# Rocketometer2148_LSM330DLC.net
KiCad netlist of a schematic drawn in EAGLE
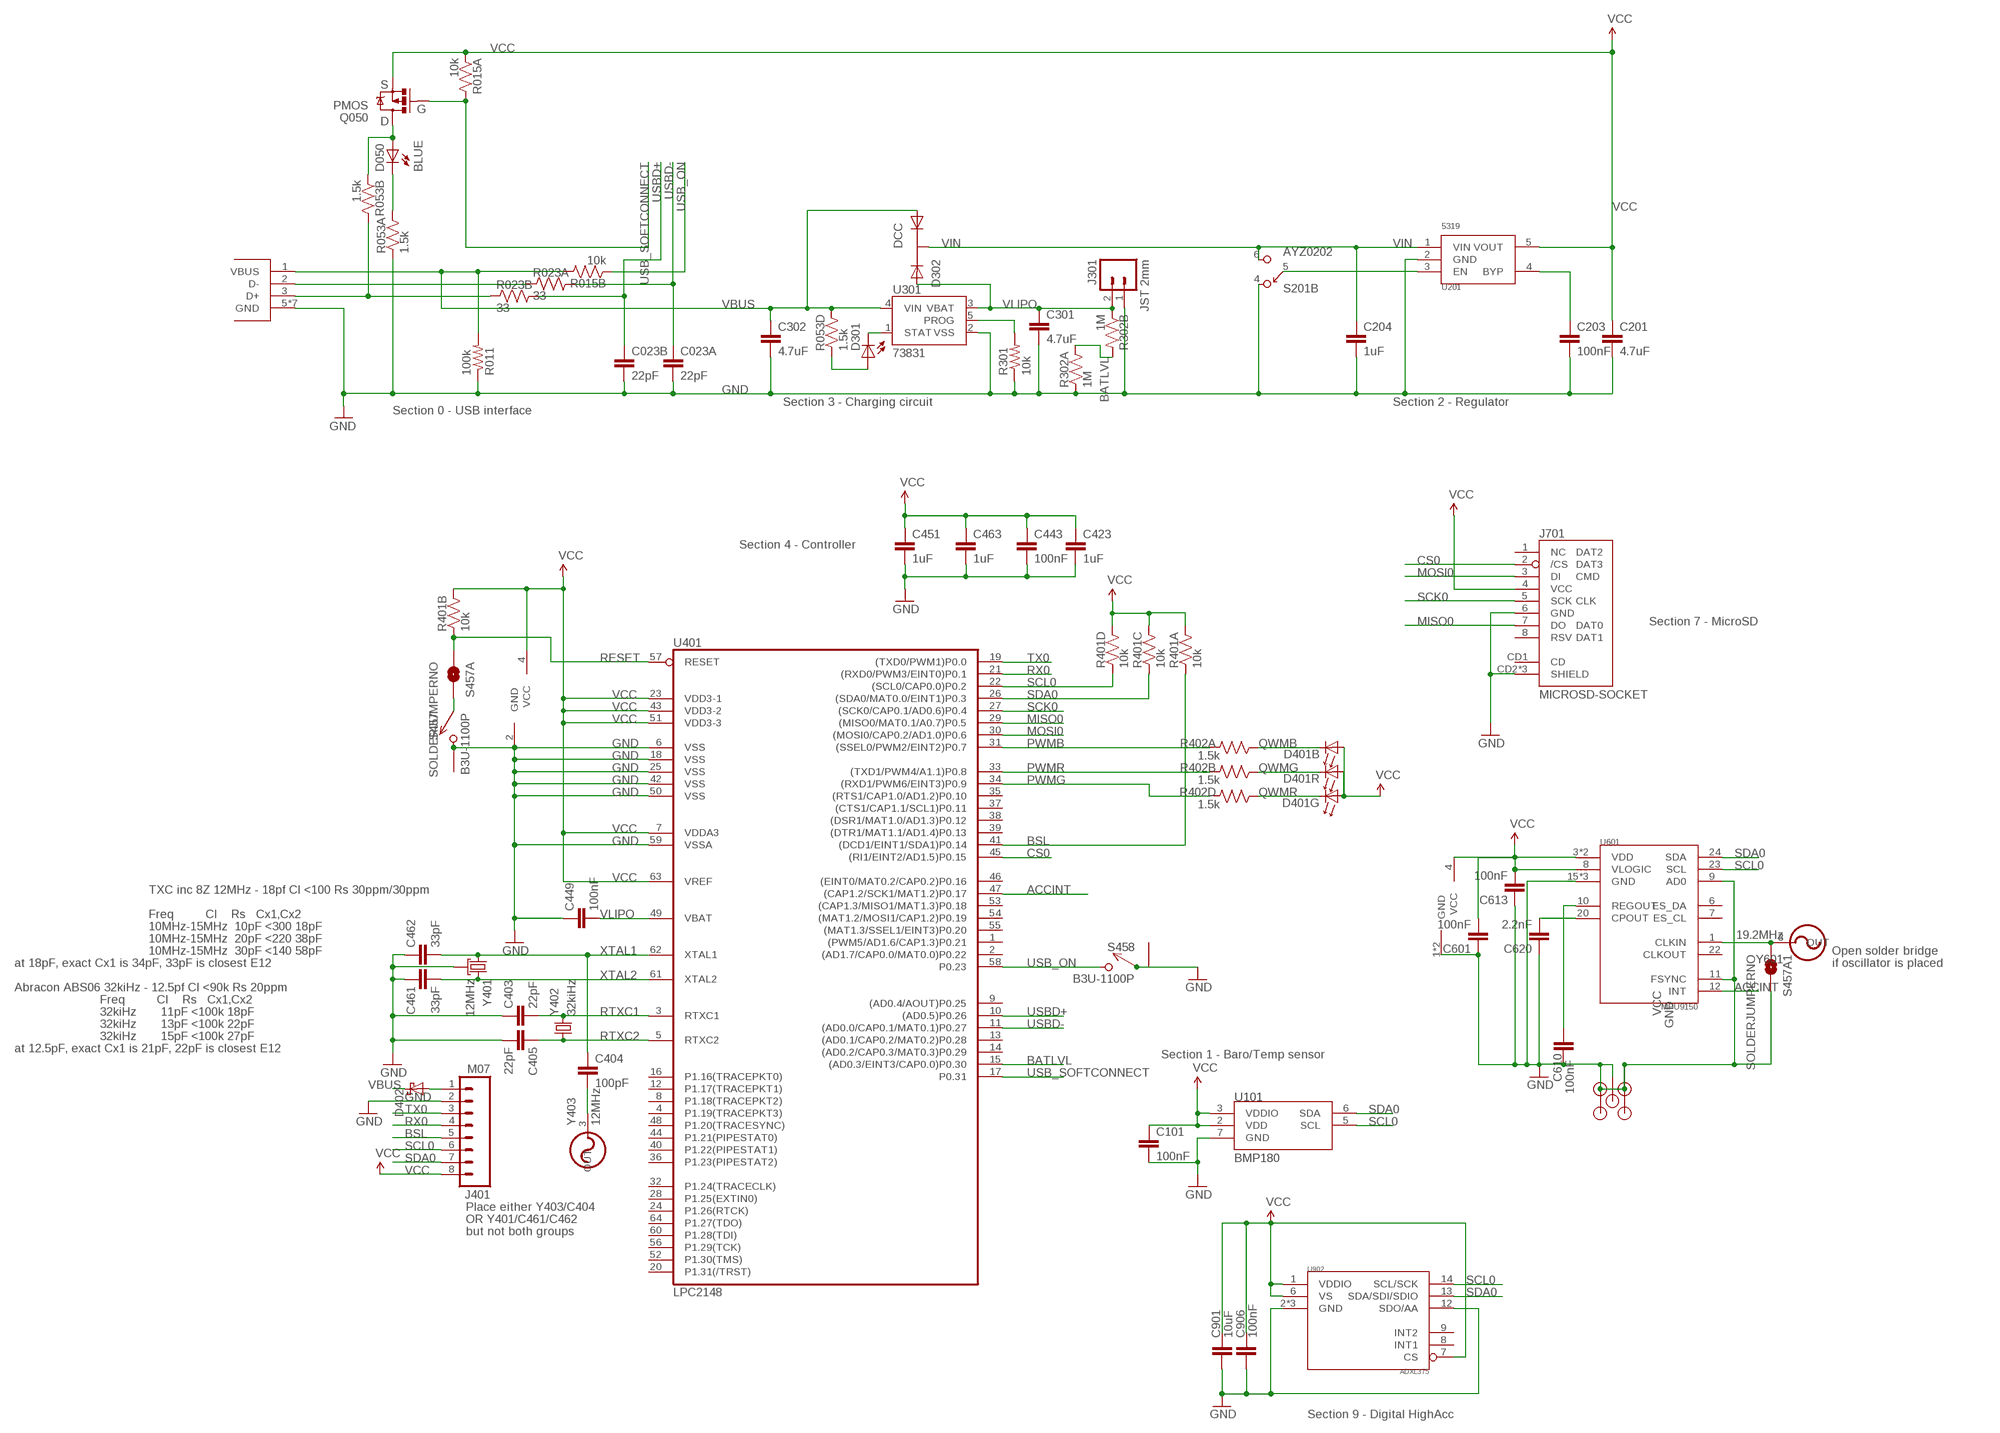
[diagram p0: schematic, sheet 1]

(export (version "E")
  (design (tool "Eeschema 10.0.6"))
  (components
    (comp (ref "C023")
      (value "22pF")
      (footprint "eagle-import:CKCM25")
      (fields (field (name "DIGIKEY") "445-1860-1-ND"))
      (libsource (lib "eagle-import") (part "CKCM25"))
    )
    (comp (ref "C101")
      (value "100nF")
      (footprint "eagle-import:0402-CAP")
      (libsource (lib "eagle-import") (part "CAP0402-CAP"))
    )
    (comp (ref "C201")
      (value "4.7uF")
      (footprint "eagle-import:0402-CAP")
      (libsource (lib "eagle-import") (part "CAP0402-CAP"))
    )
    (comp (ref "C203")
      (value "100nF")
      (footprint "eagle-import:0402-CAP")
      (libsource (lib "eagle-import") (part "CAP0402-CAP"))
    )
    (comp (ref "C204")
      (value "1uF")
      (footprint "eagle-import:0402-CAP")
      (libsource (lib "eagle-import") (part "CAP0402-CAP"))
    )
    (comp (ref "C301")
      (value "4.7uF")
      (footprint "eagle-import:0402-CAP")
      (libsource (lib "eagle-import") (part "CAP0402-CAP"))
    )
    (comp (ref "C302")
      (value "4.7uF")
      (footprint "eagle-import:0402-CAP")
      (libsource (lib "eagle-import") (part "CAP0402-CAP"))
    )
    (comp (ref "C403")
      (value "22pF")
      (footprint "eagle-import:0402-CAP")
      (libsource (lib "eagle-import") (part "CAP0402-CAP"))
    )
    (comp (ref "C404")
      (value "100pF")
      (footprint "eagle-import:0402-CAP")
      (libsource (lib "eagle-import") (part "CAP0402-CAP"))
    )
    (comp (ref "C405")
      (value "22pF")
      (footprint "eagle-import:0402-CAP")
      (libsource (lib "eagle-import") (part "CAP0402-CAP"))
    )
    (comp (ref "C423")
      (value "1uF")
      (footprint "eagle-import:0402-CAP")
      (libsource (lib "eagle-import") (part "CAP0402-CAP"))
    )
    (comp (ref "C443")
      (value "100nF")
      (footprint "eagle-import:0402-CAP")
      (libsource (lib "eagle-import") (part "CAP0402-CAP"))
    )
    (comp (ref "C449")
      (value "100nF")
      (footprint "eagle-import:0402-CAP")
      (libsource (lib "eagle-import") (part "CAP0402-CAP"))
    )
    (comp (ref "C451")
      (value "1uF")
      (footprint "eagle-import:0402-CAP")
      (libsource (lib "eagle-import") (part "CAP0402-CAP"))
    )
    (comp (ref "C461")
      (value "33pF")
      (footprint "eagle-import:0402-CAP")
      (libsource (lib "eagle-import") (part "CAP0402-CAP"))
    )
    (comp (ref "C462")
      (value "33pF")
      (footprint "eagle-import:0402-CAP")
      (libsource (lib "eagle-import") (part "CAP0402-CAP"))
    )
    (comp (ref "C463")
      (value "1uF")
      (footprint "eagle-import:0402-CAP")
      (libsource (lib "eagle-import") (part "CAP0402-CAP"))
    )
    (comp (ref "C601")
      (value "100nF")
      (footprint "eagle-import:0402-CAP")
      (libsource (lib "eagle-import") (part "CAP0402-CAP"))
    )
    (comp (ref "C610")
      (value "100nF")
      (footprint "eagle-import:0402-CAP")
      (libsource (lib "eagle-import") (part "CAP0402-CAP"))
    )
    (comp (ref "C613")
      (value "100nF")
      (footprint "eagle-import:0402-CAP")
      (libsource (lib "eagle-import") (part "CAP0402-CAP"))
    )
    (comp (ref "C620")
      (value "2.2nF")
      (footprint "eagle-import:0402-CAP")
      (libsource (lib "eagle-import") (part "CAP0402-CAP"))
    )
    (comp (ref "C901")
      (value "10uF")
      (footprint "eagle-import:0603-CAP")
      (libsource (lib "eagle-import") (part "CAP0603-CAP"))
    )
    (comp (ref "C906")
      (value "100nF")
      (footprint "eagle-import:0402-CAP")
      (libsource (lib "eagle-import") (part "SparkFun-Passives_CAP0402-CAP"))
    )
    (comp (ref "D050")
      (value "BLUE")
      (footprint "eagle-import:LED-0603")
      (libsource (lib "eagle-import") (part "LED0603"))
    )
    (comp (ref "D301")
      (value "YELLOW")
      (footprint "eagle-import:LED-0603")
      (libsource (lib "eagle-import") (part "LED0603"))
    )
    (comp (ref "D302")
      (value "DCC")
      (footprint "eagle-import:SOT-23-3")
      (libsource (lib "eagle-import") (part "PMEG2005CT"))
    )
    (comp (ref "D401")
      (value "SMLP36RGB2W(R)")
      (footprint "eagle-import:SMLP36")
      (fields (field (name "DIGIKEY") "846-1097-1-ND"))
      (libsource (lib "eagle-import") (part "SMLP36RGB2W(R)"))
    )
    (comp (ref "D402")
      (value "DIODE_SCHOTTKY")
      (footprint "eagle-import:D0603")
      (libsource (lib "eagle-import") (part "DIODE_SCHOTTKY"))
    )
    (comp (ref "J001")
      (value "USB_MICROB_JSTGCT")
      (footprint "eagle-import:USB_MICROB_3075")
      (libsource (lib "eagle-import") (part "USB_MICROB_JSTGCT"))
    )
    (comp (ref "J301")
      (value "JST 2mm")
      (footprint "eagle-import:JST-2-SMD")
      (libsource (lib "eagle-import") (part "M02-JST-2MM-SMT"))
    )
    (comp (ref "J401")
      (value "M07")
      (footprint "eagle-import:1X08")
      (libsource (lib "eagle-import") (part "M081X08"))
    )
    (comp (ref "J701")
      (value "MICROSD-SOCKET")
      (footprint "eagle-import:MICROSD-SOCKET-PP")
      (libsource (lib "eagle-import") (part "MICROSD-SOCKET"))
    )
    (comp (ref "JP1")
      (value "STANDOFF")
      (footprint "eagle-import:STANDOFF")
      (libsource (lib "eagle-import") (part "STANDOFF"))
    )
    (comp (ref "JP2")
      (value "STANDOFF")
      (footprint "eagle-import:STANDOFF")
      (libsource (lib "eagle-import") (part "STANDOFF"))
    )
    (comp (ref "JP3")
      (value "STANDOFF")
      (footprint "eagle-import:STANDOFF")
      (libsource (lib "eagle-import") (part "STANDOFF"))
    )
    (comp (ref "JP4")
      (value "STANDOFF")
      (footprint "eagle-import:STANDOFF")
      (libsource (lib "eagle-import") (part "STANDOFF"))
    )
    (comp (ref "JP5")
      (value "STANDOFF")
      (footprint "eagle-import:STANDOFF")
      (libsource (lib "eagle-import") (part "STANDOFF"))
    )
    (comp (ref "Q050")
      (value "PMOS")
      (footprint "eagle-import:SOT23-3")
      (libsource (lib "eagle-import") (part "MOSFET-PCHANNELSMD"))
    )
    (comp (ref "R011")
      (value "100k")
      (footprint "eagle-import:0402-RES")
      (libsource (lib "eagle-import") (part "RESISTOR0402-RES"))
    )
    (comp (ref "R015")
      (value "10k")
      (footprint "eagle-import:CRA02")
      (fields (field (name "DIGIKEY") "Y5103CT-ND"))
      (libsource (lib "eagle-import") (part "RP2EXB24V"))
    )
    (comp (ref "R023")
      (value "33")
      (footprint "eagle-import:CRA02")
      (libsource (lib "eagle-import") (part "RP2EXB24V"))
    )
    (comp (ref "R053")
      (value "1.5k")
      (footprint "eagle-import:CRA04")
      (fields (field (name "DIGIKEY") "CRA4S81.5KCT-ND"))
      (libsource (lib "eagle-import") (part "RP404"))
    )
    (comp (ref "R301")
      (value "10k")
      (footprint "eagle-import:0402-RES")
      (libsource (lib "eagle-import") (part "RESISTOR0402-RES"))
    )
    (comp (ref "R302")
      (value "1M")
      (footprint "eagle-import:CRA02")
      (libsource (lib "eagle-import") (part "RP2EXB24V"))
    )
    (comp (ref "R401")
      (value "10k")
      (footprint "eagle-import:CRA04")
      (fields (field (name "DIGIKEY") "CRA4S810KCT-ND"))
      (libsource (lib "eagle-import") (part "RP404"))
    )
    (comp (ref "R402")
      (value "1.5k")
      (footprint "eagle-import:CRA04")
      (fields (field (name "DIGIKEY") "CRA4S81.5KCT-ND"))
      (libsource (lib "eagle-import") (part "RP404"))
    )
    (comp (ref "S201")
      (value "AYZ0202")
      (footprint "eagle-import:AYZ0202")
      (libsource (lib "eagle-import") (part "AYZ0202"))
    )
    (comp (ref "S457")
      (value "B3U-1100P")
      (footprint "eagle-import:B3U-1100P")
      (fields (field (name "DIGIKEY") "SW1021CT-ND"))
      (libsource (lib "eagle-import") (part "B3U-1100P"))
    )
    (comp (ref "S457A")
      (value "SOLDERJUMPERNO")
      (footprint "eagle-import:SJ_2S-NO")
      (libsource (lib "eagle-import") (part "SOLDERJUMPERNO"))
    )
    (comp (ref "S457A1")
      (value "SOLDERJUMPERNO")
      (footprint "eagle-import:SJ_2S-NO")
      (libsource (lib "eagle-import") (part "SOLDERJUMPERNO"))
    )
    (comp (ref "S458")
      (value "B3U-1100P")
      (footprint "eagle-import:B3U-1100P")
      (fields (field (name "DIGIKEY") "SW1021CT-ND"))
      (libsource (lib "eagle-import") (part "B3U-1100P"))
    )
    (comp (ref "U101")
      (value "BMP180")
      (footprint "eagle-import:BMP180")
      (libsource (lib "eagle-import") (part "BMP180"))
    )
    (comp (ref "U201")
      (value "5319")
      (footprint "eagle-import:SOT-23-5")
      (libsource (lib "eagle-import") (part "MIC5319D5"))
    )
    (comp (ref "U301")
      (value "73831")
      (footprint "eagle-import:SOT23-5")
      (libsource (lib "eagle-import") (part "MCP73831"))
    )
    (comp (ref "U401")
      (value "LPC2148")
      (footprint "eagle-import:SQFP-S-10X10-64")
      (libsource (lib "eagle-import") (part "LPC213X"))
    )
    (comp (ref "U601")
      (value "MPU9150")
      (footprint "eagle-import:LLGA24")
      (libsource (lib "eagle-import") (part "MPU9150"))
    )
    (comp (ref "U902")
      (value "ADXL375")
      (footprint "eagle-import:ADXL375")
      (libsource (lib "eagle-import") (part "ADXL375"))
    )
    (comp (ref "Y401")
      (value "12MHz")
      (footprint "eagle-import:CRYSTAL_SMD_2MM_2_5MM")
      (libsource (lib "eagle-import") (part "CX2520"))
    )
    (comp (ref "Y402")
      (value "32kiHz")
      (footprint "eagle-import:ABS06")
      (libsource (lib "eagle-import") (part "ABS06"))
    )
    (comp (ref "Y403")
      (value "12MHz")
      (footprint "eagle-import:CRYSTAL_SMD_5MM_3_2MM")
      (fields (field (name "DIGIKEY") "631-1068-1-ND"))
      (libsource (lib "eagle-import") (part "OSCILLATORE35MT"))
    )
    (comp (ref "Y601")
      (value "19.2MHz")
      (footprint "eagle-import:CRYSTAL_SMD_2MM_2_5MM")
      (libsource (lib "eagle-import") (part "OSCILLATORASDMB"))
    )
  )
  (nets
    (net (code "1") (name "/ACCINT") (class "Default")
      (node (ref "U401") (pin "47") (pinfunction "(CAP1.2/SCK1/MAT1.2)P0.17_47") (pintype "bidirectional"))
      (node (ref "U601") (pin "12") (pinfunction "INT_12") (pintype "bidirectional"))
    )
    (net (code "2") (name "/BATLVL") (class "Default")
      (node (ref "R302") (pin "3") (pinfunction "2_3") (pintype "passive"))
      (node (ref "R302") (pin "4") (pinfunction "2_4") (pintype "passive"))
      (node (ref "U401") (pin "15") (pinfunction "(AD0.3/EINT3/CAP0.0)P0.30_15") (pintype "bidirectional"))
    )
    (net (code "3") (name "/BSL") (class "Default")
      (node (ref "J401") (pin "5") (pinfunction "5_5") (pintype "passive"))
      (node (ref "R401") (pin "1") (pinfunction "1_1") (pintype "passive"))
      (node (ref "U401") (pin "41") (pinfunction "(DCD1/EINT1/SDA1)P0.14_41") (pintype "bidirectional"))
    )
    (net (code "4") (name "/CS0") (class "Default")
      (node (ref "J701") (pin "2") (pinfunction "/CS_2") (pintype "bidirectional"))
      (node (ref "U401") (pin "45") (pinfunction "(RI1/EINT2/AD1.5)P0.15_45") (pintype "bidirectional"))
    )
    (net (code "5") (name "/MISO0") (class "Default")
      (node (ref "J701") (pin "7") (pinfunction "DO_7") (pintype "bidirectional"))
      (node (ref "U401") (pin "29") (pinfunction "(MISO0/MAT0.1/A0.7)P0.5_29") (pintype "bidirectional"))
    )
    (net (code "6") (name "/MOSI0") (class "Default")
      (node (ref "J701") (pin "3") (pinfunction "DI_3") (pintype "bidirectional"))
      (node (ref "U401") (pin "30") (pinfunction "(MOSI0/CAP0.2/AD1.0)P0.6_30") (pintype "bidirectional"))
    )
    (net (code "7") (name "/PWMB") (class "Default")
      (node (ref "R402") (pin "8") (pinfunction "2_8") (pintype "passive"))
      (node (ref "U401") (pin "31") (pinfunction "(SSEL0/PWM2/EINT2)P0.7_31") (pintype "bidirectional"))
    )
    (net (code "8") (name "/PWMG") (class "Default")
      (node (ref "R402") (pin "5") (pinfunction "2_5") (pintype "passive"))
      (node (ref "U401") (pin "34") (pinfunction "(RXD1/PWM6/EINT3)P0.9_34") (pintype "bidirectional"))
    )
    (net (code "9") (name "/PWMR") (class "Default")
      (node (ref "R402") (pin "7") (pinfunction "2_7") (pintype "passive"))
      (node (ref "U401") (pin "33") (pinfunction "(TXD1/PWM4/A1.1)P0.8_33") (pintype "bidirectional"))
    )
    (net (code "10") (name "/QWMB") (class "Default")
      (node (ref "D401") (pin "1") (pinfunction "C_1") (pintype "passive"))
      (node (ref "R402") (pin "1") (pinfunction "1_1") (pintype "passive"))
    )
    (net (code "11") (name "/QWMG") (class "Default")
      (node (ref "D401") (pin "5") (pinfunction "C_5") (pintype "passive"))
      (node (ref "R402") (pin "4") (pinfunction "1_4") (pintype "passive"))
    )
    (net (code "12") (name "/QWMR") (class "Default")
      (node (ref "D401") (pin "3") (pinfunction "C_3") (pintype "passive"))
      (node (ref "R402") (pin "2") (pinfunction "1_2") (pintype "passive"))
    )
    (net (code "13") (name "/RESET") (class "Default")
      (node (ref "R401") (pin "2") (pinfunction "1_2") (pintype "passive"))
      (node (ref "S457A") (pin "1") (pinfunction "1_1") (pintype "passive"))
      (node (ref "U401") (pin "57") (pinfunction "RESET_57") (pintype "input"))
    )
    (net (code "14") (name "/RTXC1") (class "Default")
      (node (ref "C403") (pin "2") (pinfunction "2_2") (pintype "passive"))
      (node (ref "U401") (pin "3") (pinfunction "RTXC1_3") (pintype "input"))
      (node (ref "Y402") (pin "2") (pinfunction "2_2") (pintype "passive"))
    )
    (net (code "15") (name "/RTXC2") (class "Default")
      (node (ref "C405") (pin "1") (pinfunction "1_1") (pintype "passive"))
      (node (ref "U401") (pin "5") (pinfunction "RTXC2_5") (pintype "output"))
      (node (ref "Y402") (pin "1") (pinfunction "1_1") (pintype "passive"))
    )
    (net (code "16") (name "/RX0") (class "Default")
      (node (ref "J401") (pin "4") (pinfunction "4_4") (pintype "passive"))
      (node (ref "U401") (pin "21") (pinfunction "(RXD0/PWM3/EINT0)P0.1_21") (pintype "bidirectional"))
    )
    (net (code "17") (name "/SCK0") (class "Default")
      (node (ref "J701") (pin "5") (pinfunction "SCK_5") (pintype "bidirectional"))
      (node (ref "U401") (pin "27") (pinfunction "(SCK0/CAP0.1/AD0.6)P0.4_27") (pintype "bidirectional"))
    )
    (net (code "18") (name "/SCL0") (class "Default")
      (node (ref "J401") (pin "6") (pinfunction "6_6") (pintype "passive"))
      (node (ref "R401") (pin "4") (pinfunction "1_4") (pintype "passive"))
      (node (ref "U101") (pin "5") (pinfunction "SCL_5") (pintype "input"))
      (node (ref "U401") (pin "22") (pinfunction "(SCL0/CAP0.0)P0.2_22") (pintype "bidirectional"))
      (node (ref "U601") (pin "23") (pinfunction "SCL_23") (pintype "bidirectional"))
      (node (ref "U902") (pin "14") (pinfunction "SCL/SCK_14") (pintype "input"))
    )
    (net (code "19") (name "/SDA0") (class "Default")
      (node (ref "J401") (pin "7") (pinfunction "7_7") (pintype "passive"))
      (node (ref "R401") (pin "3") (pinfunction "1_3") (pintype "passive"))
      (node (ref "U101") (pin "6") (pinfunction "SDA_6") (pintype "bidirectional"))
      (node (ref "U401") (pin "26") (pinfunction "(SDA0/MAT0.0/EINT1)P0.3_26") (pintype "bidirectional"))
      (node (ref "U601") (pin "24") (pinfunction "SDA_24") (pintype "bidirectional"))
      (node (ref "U902") (pin "13") (pinfunction "SDA/SDI/SDIO_13") (pintype "bidirectional"))
    )
    (net (code "20") (name "/TX0") (class "Default")
      (node (ref "J401") (pin "3") (pinfunction "3_3") (pintype "passive"))
      (node (ref "U401") (pin "19") (pinfunction "(TXD0/PWM1)P0.0_19") (pintype "bidirectional"))
    )
    (net (code "21") (name "/USBD+") (class "Default")
      (node (ref "C023") (pin "2") (pinfunction "1_2") (pintype "passive"))
      (node (ref "R023") (pin "3") (pinfunction "2_3") (pintype "passive"))
      (node (ref "U401") (pin "10") (pinfunction "(AD0.5)P0.26_10") (pintype "bidirectional"))
    )
    (net (code "22") (name "/USBD-") (class "Default")
      (node (ref "C023") (pin "1") (pinfunction "1_1") (pintype "passive"))
      (node (ref "R023") (pin "4") (pinfunction "2_4") (pintype "passive"))
      (node (ref "U401") (pin "11") (pinfunction "(AD0.0/CAP0.1/MAT0.1)P0.27_11") (pintype "bidirectional"))
    )
    (net (code "23") (name "/USB_ON") (class "Default")
      (node (ref "R015") (pin "2") (pinfunction "1_2") (pintype "passive"))
      (node (ref "S458") (pin "P$2") (pinfunction "2_P$2") (pintype "bidirectional"))
      (node (ref "U401") (pin "58") (pinfunction "P0.23_58") (pintype "bidirectional"))
    )
    (net (code "24") (name "/USB_SOFTCONNECT") (class "Default")
      (node (ref "Q050") (pin "1") (pinfunction "G_1") (pintype "passive"))
      (node (ref "R015") (pin "4") (pinfunction "2_4") (pintype "passive"))
      (node (ref "U401") (pin "17") (pinfunction "P0.31_17") (pintype "output"))
    )
    (net (code "25") (name "/VBUS") (class "Default")
      (node (ref "C302") (pin "1") (pinfunction "1_1") (pintype "passive"))
      (node (ref "D302") (pin "1") (pinfunction "A1_1") (pintype "passive"))
      (node (ref "D402") (pin "C") (pinfunction "K_C") (pintype "passive"))
      (node (ref "J001") (pin "1") (pinfunction "VBUS_1") (pintype "bidirectional"))
      (node (ref "R011") (pin "2") (pinfunction "2_2") (pintype "passive"))
      (node (ref "R015") (pin "3") (pinfunction "2_3") (pintype "passive"))
      (node (ref "R053") (pin "5") (pinfunction "2_5") (pintype "passive"))
      (node (ref "U301") (pin "4") (pinfunction "VIN_4") (pintype "power_in"))
    )
    (net (code "26") (name "/VIN") (class "Default")
      (node (ref "C204") (pin "1") (pinfunction "1_1") (pintype "passive"))
      (node (ref "D302") (pin "3") (pinfunction "K_3") (pintype "passive"))
      (node (ref "S201") (pin "6") (pinfunction "P$2_6") (pintype "bidirectional"))
      (node (ref "U201") (pin "1") (pinfunction "VIN_1") (pintype "bidirectional"))
    )
    (net (code "27") (name "/VLIPO") (class "Default")
      (node (ref "C301") (pin "1") (pinfunction "1_1") (pintype "passive"))
      (node (ref "C449") (pin "2") (pinfunction "2_2") (pintype "passive"))
      (node (ref "D302") (pin "2") (pinfunction "A2_2") (pintype "passive"))
      (node (ref "J301") (pin "2") (pinfunction "2_2") (pintype "passive"))
      (node (ref "R302") (pin "2") (pinfunction "1_2") (pintype "passive"))
      (node (ref "U301") (pin "3") (pinfunction "VBAT_3") (pintype "power_in"))
      (node (ref "U401") (pin "49") (pinfunction "VBAT_49") (pintype "power_in"))
    )
    (net (code "28") (name "/XTAL1") (class "Default")
      (node (ref "C404") (pin "1") (pinfunction "1_1") (pintype "passive"))
      (node (ref "C462") (pin "2") (pinfunction "2_2") (pintype "passive"))
      (node (ref "U401") (pin "62") (pinfunction "XTAL1_62") (pintype "input"))
      (node (ref "Y401") (pin "1") (pinfunction "1_1") (pintype "passive"))
    )
    (net (code "29") (name "/XTAL2") (class "Default")
      (node (ref "C461") (pin "2") (pinfunction "2_2") (pintype "passive"))
      (node (ref "U401") (pin "61") (pinfunction "XTAL2_61") (pintype "output"))
      (node (ref "Y401") (pin "3") (pinfunction "2_3") (pintype "passive"))
    )
    (net (code "30") (name "GND") (class "Default")
      (node (ref "C023") (pin "3") (pinfunction "2_3") (pintype "passive"))
      (node (ref "C023") (pin "4") (pinfunction "2_4") (pintype "passive"))
      (node (ref "C101") (pin "2") (pinfunction "2_2") (pintype "passive"))
      (node (ref "C201") (pin "2") (pinfunction "2_2") (pintype "passive"))
      (node (ref "C203") (pin "2") (pinfunction "2_2") (pintype "passive"))
      (node (ref "C204") (pin "2") (pinfunction "2_2") (pintype "passive"))
      (node (ref "C301") (pin "2") (pinfunction "2_2") (pintype "passive"))
      (node (ref "C302") (pin "2") (pinfunction "2_2") (pintype "passive"))
      (node (ref "C403") (pin "1") (pinfunction "1_1") (pintype "passive"))
      (node (ref "C405") (pin "2") (pinfunction "2_2") (pintype "passive"))
      (node (ref "C423") (pin "2") (pinfunction "2_2") (pintype "passive"))
      (node (ref "C443") (pin "2") (pinfunction "2_2") (pintype "passive"))
      (node (ref "C449") (pin "1") (pinfunction "1_1") (pintype "passive"))
      (node (ref "C451") (pin "2") (pinfunction "2_2") (pintype "passive"))
      (node (ref "C461") (pin "1") (pinfunction "1_1") (pintype "passive"))
      (node (ref "C462") (pin "1") (pinfunction "1_1") (pintype "passive"))
      (node (ref "C463") (pin "2") (pinfunction "2_2") (pintype "passive"))
      (node (ref "C601") (pin "1") (pinfunction "1_1") (pintype "passive"))
      (node (ref "C610") (pin "2") (pinfunction "2_2") (pintype "passive"))
      (node (ref "C613") (pin "1") (pinfunction "1_1") (pintype "passive"))
      (node (ref "C620") (pin "1") (pinfunction "1_1") (pintype "passive"))
      (node (ref "C901") (pin "2") (pinfunction "2_2") (pintype "passive"))
      (node (ref "C906") (pin "2") (pinfunction "2_2") (pintype "passive"))
      (node (ref "J001") (pin "5") (pinfunction "GND_5") (pintype "bidirectional"))
      (node (ref "J001") (pin "P$1") (pinfunction "GND_P$1") (pintype "bidirectional"))
      (node (ref "J001") (pin "P$10") (pinfunction "GND_P$10") (pintype "bidirectional"))
      (node (ref "J001") (pin "P$2") (pinfunction "GND_P$2") (pintype "bidirectional"))
      (node (ref "J001") (pin "P$3") (pinfunction "GND_P$3") (pintype "bidirectional"))
      (node (ref "J001") (pin "P$4") (pinfunction "GND_P$4") (pintype "bidirectional"))
      (node (ref "J001") (pin "P$8") (pinfunction "GND_P$8") (pintype "bidirectional"))
      (node (ref "J301") (pin "1") (pinfunction "1_1") (pintype "passive"))
      (node (ref "J401") (pin "2") (pinfunction "2_2") (pintype "passive"))
      (node (ref "J701") (pin "6") (pinfunction "GND_6") (pintype "bidirectional"))
      (node (ref "J701") (pin "CD2") (pinfunction "SHIELD_CD2") (pintype "bidirectional"))
      (node (ref "J701") (pin "GND1") (pinfunction "SHIELD_GND1") (pintype "bidirectional"))
      (node (ref "J701") (pin "GND3") (pinfunction "SHIELD_GND3") (pintype "bidirectional"))
      (node (ref "JP1") (pin "P$1") (pinfunction "P$1_P$1") (pintype "bidirectional"))
      (node (ref "JP2") (pin "P$1") (pinfunction "P$1_P$1") (pintype "bidirectional"))
      (node (ref "JP3") (pin "P$1") (pinfunction "P$1_P$1") (pintype "bidirectional"))
      (node (ref "JP4") (pin "P$1") (pinfunction "P$1_P$1") (pintype "bidirectional"))
      (node (ref "JP5") (pin "P$1") (pinfunction "P$1_P$1") (pintype "bidirectional"))
      (node (ref "R011") (pin "1") (pinfunction "1_1") (pintype "passive"))
      (node (ref "R053") (pin "1") (pinfunction "1_1") (pintype "passive"))
      (node (ref "R301") (pin "1") (pinfunction "1_1") (pintype "passive"))
      (node (ref "R302") (pin "1") (pinfunction "1_1") (pintype "passive"))
      (node (ref "S201") (pin "4") (pinfunction "P$1_4") (pintype "bidirectional"))
      (node (ref "S457") (pin "P$2") (pinfunction "2_P$2") (pintype "bidirectional"))
      (node (ref "S457") (pin "P$3") (pinfunction "1_P$3") (pintype "bidirectional"))
      (node (ref "S457A1") (pin "2") (pinfunction "2_2") (pintype "passive"))
      (node (ref "S458") (pin "P$1") (pinfunction "1_P$1") (pintype "bidirectional"))
      (node (ref "S458") (pin "P$3") (pinfunction "1_P$3") (pintype "bidirectional"))
      (node (ref "U101") (pin "7") (pinfunction "GND_7") (pintype "power_in"))
      (node (ref "U201") (pin "2") (pinfunction "GND_2") (pintype "bidirectional"))
      (node (ref "U301") (pin "2") (pinfunction "VSS_2") (pintype "power_in"))
      (node (ref "U401") (pin "18") (pinfunction "VSS_18") (pintype "power_in"))
      (node (ref "U401") (pin "25") (pinfunction "VSS_25") (pintype "power_in"))
      (node (ref "U401") (pin "42") (pinfunction "VSS_42") (pintype "power_in"))
      (node (ref "U401") (pin "50") (pinfunction "VSS_50") (pintype "power_in"))
      (node (ref "U401") (pin "59") (pinfunction "VSSA_59") (pintype "power_in"))
      (node (ref "U401") (pin "6") (pinfunction "VSS_6") (pintype "power_in"))
      (node (ref "U601") (pin "11") (pinfunction "FSYNC_11") (pintype "bidirectional"))
      (node (ref "U601") (pin "15") (pinfunction "GND_15") (pintype "bidirectional"))
      (node (ref "U601") (pin "17") (pinfunction "GND_17") (pintype "bidirectional"))
      (node (ref "U601") (pin "18") (pinfunction "GND_18") (pintype "bidirectional"))
      (node (ref "U601") (pin "9") (pinfunction "AD0_9") (pintype "bidirectional"))
      (node (ref "U902") (pin "12") (pinfunction "SDO/AA_12") (pintype "bidirectional"))
      (node (ref "U902") (pin "2") (pinfunction "GND_2") (pintype "power_in"))
      (node (ref "U902") (pin "4") (pinfunction "GND_4") (pintype "power_in"))
      (node (ref "U902") (pin "5") (pinfunction "GND_5") (pintype "power_in"))
      (node (ref "Y401") (pin "2") (pinfunction "GND_2") (pintype "passive"))
      (node (ref "Y401") (pin "4") (pinfunction "GND_4") (pintype "passive"))
      (node (ref "Y403") (pin "2") (pinfunction "GND_2") (pintype "bidirectional"))
      (node (ref "Y601") (pin "1") (pinfunction "GND_1") (pintype "bidirectional"))
      (node (ref "Y601") (pin "2") (pinfunction "GND_2") (pintype "bidirectional"))
    )
    (net (code "31") (name "Net-(D402-PadA)") (class "Default")
      (node (ref "D402") (pin "A") (pinfunction "A_A") (pintype "passive"))
      (node (ref "J401") (pin "1") (pinfunction "1_1") (pintype "passive"))
    )
    (net (code "32") (name "Net-(J001-D+)") (class "Default")
      (node (ref "J001") (pin "3") (pinfunction "D+_3") (pintype "bidirectional"))
      (node (ref "R023") (pin "2") (pinfunction "1_2") (pintype "passive"))
      (node (ref "R053") (pin "7") (pinfunction "2_7") (pintype "passive"))
    )
    (net (code "33") (name "Net-(J001-D-)") (class "Default")
      (node (ref "J001") (pin "2") (pinfunction "D-_2") (pintype "bidirectional"))
      (node (ref "R023") (pin "1") (pinfunction "1_1") (pintype "passive"))
    )
    (net (code "34") (name "Net-(Q050-D)") (class "Default")
      (node (ref "D050") (pin "A") (pinfunction "A_A") (pintype "passive"))
      (node (ref "Q050") (pin "3") (pinfunction "D_3") (pintype "passive"))
      (node (ref "R053") (pin "2") (pinfunction "1_2") (pintype "passive"))
    )
    (net (code "35") (name "Net-(R053A-2)") (class "Default")
      (node (ref "D050") (pin "C") (pinfunction "C_C") (pintype "passive"))
      (node (ref "R053") (pin "8") (pinfunction "2_8") (pintype "passive"))
    )
    (net (code "36") (name "Net-(R053D-1)") (class "Default")
      (node (ref "D301") (pin "A") (pinfunction "A_A") (pintype "passive"))
      (node (ref "R053") (pin "4") (pinfunction "1_4") (pintype "passive"))
    )
    (net (code "37") (name "Net-(S201B-P$3)") (class "Default")
      (node (ref "S201") (pin "5") (pinfunction "P$3_5") (pintype "bidirectional"))
      (node (ref "U201") (pin "3") (pinfunction "EN_3") (pintype "bidirectional"))
    )
    (net (code "38") (name "Net-(S457B-1)") (class "Default")
      (node (ref "S457") (pin "P$1") (pinfunction "1_P$1") (pintype "bidirectional"))
      (node (ref "S457A") (pin "2") (pinfunction "2_2") (pintype "passive"))
    )
    (net (code "39") (name "Net-(U201-BYP)") (class "Default")
      (node (ref "C203") (pin "1") (pinfunction "1_1") (pintype "passive"))
      (node (ref "U201") (pin "4") (pinfunction "BYP_4") (pintype "bidirectional"))
    )
    (net (code "40") (name "Net-(U301-PROG)") (class "Default")
      (node (ref "R301") (pin "2") (pinfunction "2_2") (pintype "passive"))
      (node (ref "U301") (pin "5") (pinfunction "PROG_5") (pintype "input"))
    )
    (net (code "41") (name "Net-(U301-STAT)") (class "Default")
      (node (ref "D301") (pin "C") (pinfunction "C_C") (pintype "passive"))
      (node (ref "U301") (pin "1") (pinfunction "STAT_1") (pintype "output"))
    )
    (net (code "42") (name "Net-(U601-CLKIN)") (class "Default")
      (node (ref "S457A1") (pin "1") (pinfunction "1_1") (pintype "passive"))
      (node (ref "U601") (pin "1") (pinfunction "CLKIN_1") (pintype "bidirectional"))
      (node (ref "Y601") (pin "3") (pinfunction "OUT_3") (pintype "bidirectional"))
    )
    (net (code "43") (name "Net-(U601-CPOUT)") (class "Default")
      (node (ref "C620") (pin "2") (pinfunction "2_2") (pintype "passive"))
      (node (ref "U601") (pin "20") (pinfunction "CPOUT_20") (pintype "bidirectional"))
    )
    (net (code "44") (name "Net-(U601-REGOUT)") (class "Default")
      (node (ref "C610") (pin "1") (pinfunction "1_1") (pintype "passive"))
      (node (ref "U601") (pin "10") (pinfunction "REGOUT_10") (pintype "bidirectional"))
    )
    (net (code "45") (name "Net-(Y403A-OUT)") (class "Default")
      (node (ref "C404") (pin "2") (pinfunction "2_2") (pintype "passive"))
      (node (ref "Y403") (pin "3") (pinfunction "OUT_3") (pintype "bidirectional"))
    )
    (net (code "46") (name "VCC") (class "Default")
      (node (ref "C101") (pin "1") (pinfunction "1_1") (pintype "passive"))
      (node (ref "C201") (pin "1") (pinfunction "1_1") (pintype "passive"))
      (node (ref "C423") (pin "1") (pinfunction "1_1") (pintype "passive"))
      (node (ref "C443") (pin "1") (pinfunction "1_1") (pintype "passive"))
      (node (ref "C451") (pin "1") (pinfunction "1_1") (pintype "passive"))
      (node (ref "C463") (pin "1") (pinfunction "1_1") (pintype "passive"))
      (node (ref "C601") (pin "2") (pinfunction "2_2") (pintype "passive"))
      (node (ref "C613") (pin "2") (pinfunction "2_2") (pintype "passive"))
      (node (ref "C901") (pin "1") (pinfunction "1_1") (pintype "passive"))
      (node (ref "C906") (pin "1") (pinfunction "1_1") (pintype "passive"))
      (node (ref "D401") (pin "2") (pinfunction "A_2") (pintype "passive"))
      (node (ref "D401") (pin "4") (pinfunction "A_4") (pintype "passive"))
      (node (ref "D401") (pin "6") (pinfunction "A_6") (pintype "passive"))
      (node (ref "J401") (pin "8") (pinfunction "8_8") (pintype "passive"))
      (node (ref "J701") (pin "4") (pinfunction "VCC_4") (pintype "bidirectional"))
      (node (ref "Q050") (pin "2") (pinfunction "S_2") (pintype "passive"))
      (node (ref "R015") (pin "1") (pinfunction "1_1") (pintype "passive"))
      (node (ref "R401") (pin "5") (pinfunction "2_5") (pintype "passive"))
      (node (ref "R401") (pin "6") (pinfunction "2_6") (pintype "passive"))
      (node (ref "R401") (pin "7") (pinfunction "2_7") (pintype "passive"))
      (node (ref "R401") (pin "8") (pinfunction "2_8") (pintype "passive"))
      (node (ref "U101") (pin "2") (pinfunction "VDD_2") (pintype "power_in"))
      (node (ref "U101") (pin "3") (pinfunction "VDDIO_3") (pintype "power_in"))
      (node (ref "U201") (pin "5") (pinfunction "VOUT_5") (pintype "bidirectional"))
      (node (ref "U401") (pin "23") (pinfunction "VDD3-1_23") (pintype "power_in"))
      (node (ref "U401") (pin "43") (pinfunction "VDD3-2_43") (pintype "power_in"))
      (node (ref "U401") (pin "51") (pinfunction "VDD3-3_51") (pintype "power_in"))
      (node (ref "U401") (pin "63") (pinfunction "VREF_63") (pintype "input"))
      (node (ref "U401") (pin "7") (pinfunction "VDDA3_7") (pintype "power_in"))
      (node (ref "U601") (pin "13") (pinfunction "VDD_13") (pintype "bidirectional"))
      (node (ref "U601") (pin "3") (pinfunction "VDD_3") (pintype "bidirectional"))
      (node (ref "U601") (pin "8") (pinfunction "VLOGIC_8") (pintype "bidirectional"))
      (node (ref "U902") (pin "1") (pinfunction "VDDIO_1") (pintype "power_in"))
      (node (ref "U902") (pin "6") (pinfunction "VS_6") (pintype "power_in"))
      (node (ref "U902") (pin "7") (pinfunction "CS_7") (pintype "input"))
      (node (ref "Y403") (pin "4") (pinfunction "VCC_4") (pintype "bidirectional"))
      (node (ref "Y601") (pin "4") (pinfunction "VCC_4") (pintype "bidirectional"))
    )
    (net (code "47") (name "unconnected-(J701-CD-PadCD1)") (class "Default")
      (node (ref "J701") (pin "CD1") (pinfunction "CD_CD1") (pintype "bidirectional"))
    )
    (net (code "48") (name "unconnected-(J701-NC-Pad1)") (class "Default")
      (node (ref "J701") (pin "1") (pinfunction "NC_1") (pintype "bidirectional"))
    )
    (net (code "49") (name "unconnected-(J701-RSV-Pad8)") (class "Default")
      (node (ref "J701") (pin "8") (pinfunction "RSV_8") (pintype "bidirectional"))
    )
    (net (code "50") (name "unconnected-(U401-(AD0.1{slash}CAP0.2{slash}MAT0.2)P0.28-Pad13)") (class "Default")
      (node (ref "U401") (pin "13") (pinfunction "(AD0.1/CAP0.2/MAT0.2)P0.28_13") (pintype "bidirectional"))
    )
    (net (code "51") (name "unconnected-(U401-(AD0.2{slash}CAP0.3{slash}MAT0.3)P0.29-Pad14)") (class "Default")
      (node (ref "U401") (pin "14") (pinfunction "(AD0.2/CAP0.3/MAT0.3)P0.29_14") (pintype "bidirectional"))
    )
    (net (code "52") (name "unconnected-(U401-(AD0.4{slash}AOUT)P0.25-Pad9)") (class "Default")
      (node (ref "U401") (pin "9") (pinfunction "(AD0.4/AOUT)P0.25_9") (pintype "bidirectional"))
    )
    (net (code "53") (name "unconnected-(U401-(AD1.7{slash}CAP0.0{slash}MAT0.0)P0.22-Pad2)") (class "Default")
      (node (ref "U401") (pin "2") (pinfunction "(AD1.7/CAP0.0/MAT0.0)P0.22_2") (pintype "bidirectional"))
    )
    (net (code "54") (name "unconnected-(U401-(CAP1.3{slash}MISO1{slash}MAT1.3)P0.18-Pad53)") (class "Default")
      (node (ref "U401") (pin "53") (pinfunction "(CAP1.3/MISO1/MAT1.3)P0.18_53") (pintype "bidirectional"))
    )
    (net (code "55") (name "unconnected-(U401-(CTS1{slash}CAP1.1{slash}SCL1)P0.11-Pad37)") (class "Default")
      (node (ref "U401") (pin "37") (pinfunction "(CTS1/CAP1.1/SCL1)P0.11_37") (pintype "bidirectional"))
    )
    (net (code "56") (name "unconnected-(U401-(DSR1{slash}MAT1.0{slash}AD1.3)P0.12-Pad38)") (class "Default")
      (node (ref "U401") (pin "38") (pinfunction "(DSR1/MAT1.0/AD1.3)P0.12_38") (pintype "bidirectional"))
    )
    (net (code "57") (name "unconnected-(U401-(DTR1{slash}MAT1.1{slash}AD1.4)P0.13-Pad39)") (class "Default")
      (node (ref "U401") (pin "39") (pinfunction "(DTR1/MAT1.1/AD1.4)P0.13_39") (pintype "bidirectional"))
    )
    (net (code "58") (name "unconnected-(U401-(EINT0{slash}MAT0.2{slash}CAP0.2)P0.16-Pad46)") (class "Default")
      (node (ref "U401") (pin "46") (pinfunction "(EINT0/MAT0.2/CAP0.2)P0.16_46") (pintype "bidirectional"))
    )
    (net (code "59") (name "unconnected-(U401-(MAT1.2{slash}MOSI1{slash}CAP1.2)P0.19-Pad54)") (class "Default")
      (node (ref "U401") (pin "54") (pinfunction "(MAT1.2/MOSI1/CAP1.2)P0.19_54") (pintype "bidirectional"))
    )
    (net (code "60") (name "unconnected-(U401-(MAT1.3{slash}SSEL1{slash}EINT3)P0.20-Pad55)") (class "Default")
      (node (ref "U401") (pin "55") (pinfunction "(MAT1.3/SSEL1/EINT3)P0.20_55") (pintype "bidirectional"))
    )
    (net (code "61") (name "unconnected-(U401-(PWM5{slash}AD1.6{slash}CAP1.3)P0.21-Pad1)") (class "Default")
      (node (ref "U401") (pin "1") (pinfunction "(PWM5/AD1.6/CAP1.3)P0.21_1") (pintype "bidirectional"))
    )
    (net (code "62") (name "unconnected-(U401-(RTS1{slash}CAP1.0{slash}AD1.2)P0.10-Pad35)") (class "Default")
      (node (ref "U401") (pin "35") (pinfunction "(RTS1/CAP1.0/AD1.2)P0.10_35") (pintype "bidirectional"))
    )
    (net (code "63") (name "unconnected-(U401-P1.16(TRACEPKT0)-Pad16)") (class "Default")
      (node (ref "U401") (pin "16") (pinfunction "P1.16(TRACEPKT0)_16") (pintype "bidirectional"))
    )
    (net (code "64") (name "unconnected-(U401-P1.17(TRACEPKT1)-Pad12)") (class "Default")
      (node (ref "U401") (pin "12") (pinfunction "P1.17(TRACEPKT1)_12") (pintype "bidirectional"))
    )
    (net (code "65") (name "unconnected-(U401-P1.18(TRACEPKT2)-Pad8)") (class "Default")
      (node (ref "U401") (pin "8") (pinfunction "P1.18(TRACEPKT2)_8") (pintype "bidirectional"))
    )
    (net (code "66") (name "unconnected-(U401-P1.19(TRACEPKT3)-Pad4)") (class "Default")
      (node (ref "U401") (pin "4") (pinfunction "P1.19(TRACEPKT3)_4") (pintype "bidirectional"))
    )
    (net (code "67") (name "unconnected-(U401-P1.20(TRACESYNC)-Pad48)") (class "Default")
      (node (ref "U401") (pin "48") (pinfunction "P1.20(TRACESYNC)_48") (pintype "bidirectional"))
    )
    (net (code "68") (name "unconnected-(U401-P1.21(PIPESTAT0)-Pad44)") (class "Default")
      (node (ref "U401") (pin "44") (pinfunction "P1.21(PIPESTAT0)_44") (pintype "bidirectional"))
    )
    (net (code "69") (name "unconnected-(U401-P1.22(PIPESTAT1)-Pad40)") (class "Default")
      (node (ref "U401") (pin "40") (pinfunction "P1.22(PIPESTAT1)_40") (pintype "bidirectional"))
    )
    (net (code "70") (name "unconnected-(U401-P1.23(PIPESTAT2)-Pad36)") (class "Default")
      (node (ref "U401") (pin "36") (pinfunction "P1.23(PIPESTAT2)_36") (pintype "bidirectional"))
    )
    (net (code "71") (name "unconnected-(U401-P1.24(TRACECLK)-Pad32)") (class "Default")
      (node (ref "U401") (pin "32") (pinfunction "P1.24(TRACECLK)_32") (pintype "bidirectional"))
    )
    (net (code "72") (name "unconnected-(U401-P1.25(EXTIN0)-Pad28)") (class "Default")
      (node (ref "U401") (pin "28") (pinfunction "P1.25(EXTIN0)_28") (pintype "bidirectional"))
    )
    (net (code "73") (name "unconnected-(U401-P1.26(RTCK)-Pad24)") (class "Default")
      (node (ref "U401") (pin "24") (pinfunction "P1.26(RTCK)_24") (pintype "bidirectional"))
    )
    (net (code "74") (name "unconnected-(U401-P1.27(TDO)-Pad64)") (class "Default")
      (node (ref "U401") (pin "64") (pinfunction "P1.27(TDO)_64") (pintype "bidirectional"))
    )
    (net (code "75") (name "unconnected-(U401-P1.28(TDI)-Pad60)") (class "Default")
      (node (ref "U401") (pin "60") (pinfunction "P1.28(TDI)_60") (pintype "bidirectional"))
    )
    (net (code "76") (name "unconnected-(U401-P1.29(TCK)-Pad56)") (class "Default")
      (node (ref "U401") (pin "56") (pinfunction "P1.29(TCK)_56") (pintype "bidirectional"))
    )
    (net (code "77") (name "unconnected-(U401-P1.30(TMS)-Pad52)") (class "Default")
      (node (ref "U401") (pin "52") (pinfunction "P1.30(TMS)_52") (pintype "bidirectional"))
    )
    (net (code "78") (name "unconnected-(U401-P1.31({slash}TRST)-Pad20)") (class "Default")
      (node (ref "U401") (pin "20") (pinfunction "P1.31(/TRST)_20") (pintype "bidirectional"))
    )
    (net (code "79") (name "unconnected-(U601-CLKOUT-Pad22)") (class "Default")
      (node (ref "U601") (pin "22") (pinfunction "CLKOUT_22") (pintype "bidirectional"))
    )
    (net (code "80") (name "unconnected-(U601-ES_CL-Pad7)") (class "Default")
      (node (ref "U601") (pin "7") (pinfunction "ES_CL_7") (pintype "bidirectional"))
    )
    (net (code "81") (name "unconnected-(U601-ES_DA-Pad6)") (class "Default")
      (node (ref "U601") (pin "6") (pinfunction "ES_DA_6") (pintype "bidirectional"))
    )
    (net (code "82") (name "unconnected-(U902-INT1-Pad8)") (class "Default")
      (node (ref "U902") (pin "8") (pinfunction "INT1_8") (pintype "output"))
    )
    (net (code "83") (name "unconnected-(U902-INT2-Pad9)") (class "Default")
      (node (ref "U902") (pin "9") (pinfunction "INT2_9") (pintype "output"))
    )
  )
)
